# Sheet2.net
KiCad netlist of a schematic drawn in Altium Designer
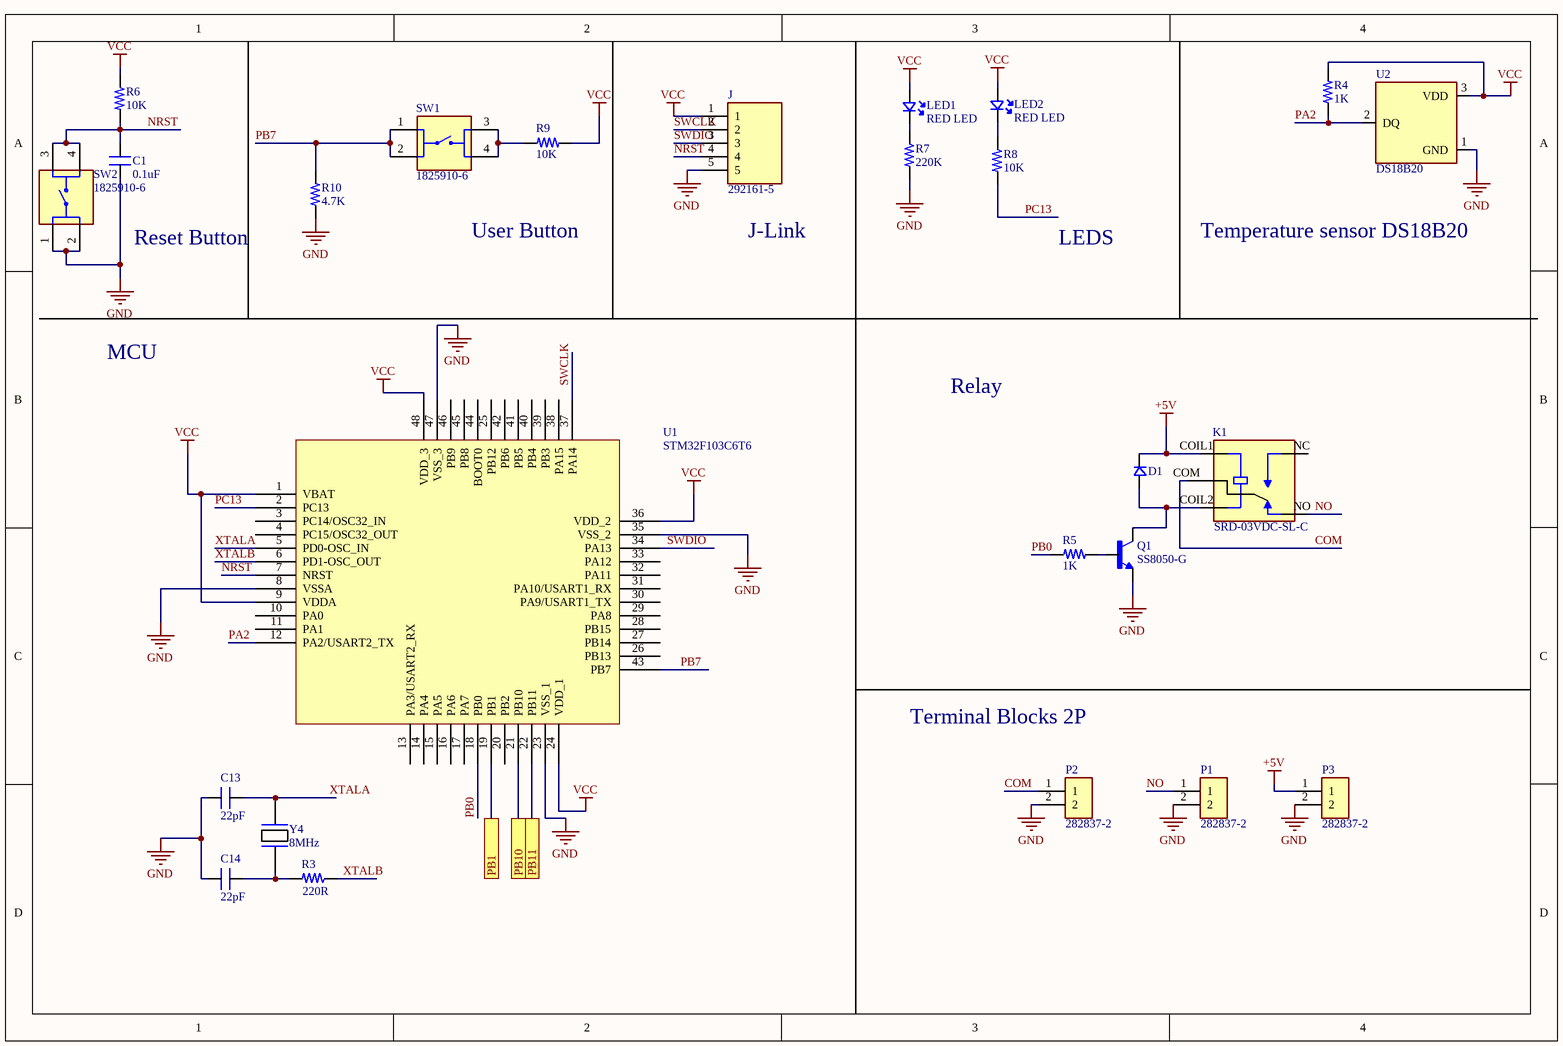
[diagram p0: Sheet2.SchDoc]

(export (version "E")
  (design (tool "Eeschema 10.0.6"))
  (components
    (comp (ref "C1")
      (value "0.1uF")
      (footprint "CAP_0805")
      (description "0.1µF ±5% 50V Ceramic Capacitor X7R 0805 (2012 Metric)")
      (fields
        (field (name "MANUFACTURER") "KEMET")
        (field (name "MANUFACTURING PART NUMBER") "C0805C104J5RACTU")
      )
      (libsource (lib "STM_SCH_LIB") (part "CAP_0.1uF-50V-5%-0805"))
    )
    (comp (ref "C13")
      (value "22pF")
      (footprint "CAP_0805")
      (description "22pF ±5% 50V Ceramic Capacitor C0G, NP0 0805 (2012 Metric)")
      (fields
        (field (name "MANUFACTURER") "KEMET")
        (field (name "MANUFACTURER PART NUMBER") "C0805C220J5GACTU")
      )
      (libsource (lib "STM_SCH_LIB") (part "CAP_22pF-50V-5%-0805"))
    )
    (comp (ref "C14")
      (value "22pF")
      (footprint "CAP_0805")
      (description "22pF ±5% 50V Ceramic Capacitor C0G, NP0 0805 (2012 Metric)")
      (fields
        (field (name "MANUFACTURER") "KEMET")
        (field (name "MANUFACTURER PART NUMBER") "C0805C220J5GACTU")
      )
      (libsource (lib "STM_SCH_LIB") (part "CAP_22pF-50V-5%-0805"))
    )
    (comp (ref "D1")
      (value "~")
      (footprint "DIOAD829W49L456D191")
      (description "Diode Standard 75V 200mA Surface Mount SOD-523F")
      (libsource (lib "Power_Plug") (part "1N4148"))
    )
    (comp (ref "J")
      (value "292161-5")
      (footprint "TE_292161-5")
      (description "Wire-To-Board Connector, Vertical, AMP CT Series, Through Hole, Header, 5, 2 mm")
      (fields (field (name "MF") "TE Connectivity"))
      (libsource (lib "Power_Plug") (part "292161-5"))
    )
    (comp (ref "K1")
      (value "SRD-03VDC-SL-C")
      (footprint "RELAY_SRD-03VDC-SL-C")
      (description "Relays General Purpose Non Latching 3VDC SPDT 10A (250VAC) Max 5PIN")
      (fields (field (name "MF") "Songle Relay"))
      (libsource (lib "Power_Plug") (part "SRD-03VDC-SL-C"))
    )
    (comp (ref "LED1")
      (value "RED LED")
      (footprint "LED_0805")
      (description "Red 621nm LED Indication - Discrete 2V 0805 (2012 Metric)")
      (fields
        (field (name "MANUFACTURER") "Lite-On Inc.")
        (field (name "MANUFACTURER PART NUMBER") "LTST-C170EKT")
      )
      (libsource (lib "STM_SCH_LIB") (part "LED-RED_10mA-0805"))
    )
    (comp (ref "LED2")
      (value "RED LED")
      (footprint "LED_0805")
      (description "Red 621nm LED Indication - Discrete 2V 0805 (2012 Metric)")
      (fields
        (field (name "MANUFACTURER") "Lite-On Inc.")
        (field (name "MANUFACTURER PART NUMBER") "LTST-C170EKT")
      )
      (libsource (lib "STM_SCH_LIB") (part "LED-RED_10mA-0805"))
    )
    (comp (ref "P1")
      (value "282837-2")
      (footprint "TE_282837-2")
      (description "Connector Terminal Blocks Receptacle 2 Position 5.08mm Solder Straight Thru-Hole 13.5A/Contact")
      (fields (field (name "MF") "TE Connectivity"))
      (libsource (lib "Power_Plug") (part "282837-2"))
    )
    (comp (ref "P2")
      (value "282837-2")
      (footprint "TE_282837-2")
      (description "Connector Terminal Blocks Receptacle 2 Position 5.08mm Solder Straight Thru-Hole 13.5A/Contact")
      (fields (field (name "MF") "TE Connectivity"))
      (libsource (lib "Power_Plug") (part "282837-2"))
    )
    (comp (ref "P3")
      (value "282837-2")
      (footprint "TE_282837-2")
      (description "Connector Terminal Blocks Receptacle 2 Position 5.08mm Solder Straight Thru-Hole 13.5A/Contact")
      (fields (field (name "MF") "TE Connectivity"))
      (libsource (lib "Power_Plug") (part "282837-2"))
    )
    (comp (ref "Q1")
      (value "SS8050-G")
      (footprint "TRANS_SS8050-G")
      (description "Bipolar (BJT) Transistor NPN 25 V 1.5 A 100MHz 300 mW Surface Mount SOT-23-3")
      (fields (field (name "DIGI-KEY_PART_NUMBER") "641-1790-2-ND") (field (name "MP") "SS8050G"))
      (libsource (lib "Power_Plug") (part "SS8050-G"))
    )
    (comp (ref "R3")
      (value "220R")
      (footprint "RES_0805")
      (description "220 Ohms ±1% 0.125W, 1/8W Chip Resistor 0805 (2012 Metric) Thick Film")
      (fields
        (field (name "MANUFACTURER") "TE Connectivity Passive Product")
        (field (name "MANUFACTURING PART NUMBER") "CRG0805F1K5")
      )
      (libsource (lib "Power_Plug") (part "RES_220R-0.125W-1%-0805_1_1_1"))
    )
    (comp (ref "R4")
      (value "1K")
      (footprint "RES_0805")
      (description "4.7 kOhms ±1% 0.125W, 1/8W Chip Resistor 0805 (2012 Metric) Thick Film")
      (fields
        (field (name "MANUFACTURER") "TE Connectivity Passive Product")
        (field (name "MANUFACTURING PART NUMBER") "CRG0805F1K5")
      )
      (libsource (lib "Power_Plug") (part "RES_4.7K-0.125W-1%-0805"))
    )
    (comp (ref "R5")
      (value "1K")
      (footprint "RES_0805")
      (description "10 kOhms ±1% 0.125W, 1/8W Chip Resistor 0805 (2012 Metric) Moisture Resistant Thick Film")
      (fields
        (field (name "MANUFACTURER") "Yageo")
        (field (name "MANUFACTURING PART NUMBER") "RC0805FR-0710KL")
      )
      (libsource (lib "Power_Plug") (part "RES_10K-0.125W-1%-0805"))
    )
    (comp (ref "R6")
      (value "10K")
      (footprint "RES_0805")
      (description "10 kOhms ±1% 0.125W, 1/8W Chip Resistor 0805 (2012 Metric) Moisture Resistant Thick Film")
      (fields
        (field (name "MANUFACTURER") "Yageo")
        (field (name "MANUFACTURING PART NUMBER") "RC0805FR-0710KL")
      )
      (libsource (lib "STM_SCH_LIB") (part "RES_10K-0.125W-1%-0805"))
    )
    (comp (ref "R7")
      (value "220K")
      (footprint "RES_0805")
      (description "1 kOhms ±1% 0.125W, 1/8W Chip Resistor 0805 (2012 Metric) Moisture Resistant Thick Film")
      (fields (field (name "MANUFACTURER") "垈㎵á") (field (name "MANUFACTURER PART NUMBER") "RC0805FR-071KL"))
      (libsource (lib "STM_SCH_LIB") (part "RES_1K-0.125W-1%-0805"))
    )
    (comp (ref "R8")
      (value "10K")
      (footprint "RES_0805")
      (description "10 kOhms ±1% 0.125W, 1/8W Chip Resistor 0805 (2012 Metric) Moisture Resistant Thick Film")
      (fields
        (field (name "MANUFACTURER") "Yageo")
        (field (name "MANUFACTURING PART NUMBER") "RC0805FR-0710KL")
      )
      (libsource (lib "Power_Plug") (part "RES_10K-0.125W-1%-0805"))
    )
    (comp (ref "R9")
      (value "10K")
      (footprint "RES_0805")
      (description "220 Ohms ±1% 0.125W, 1/8W Chip Resistor 0805 (2012 Metric) Thick Film")
      (fields
        (field (name "MANUFACTURER") "TE Connectivity Passive Product")
        (field (name "MANUFACTURING PART NUMBER") "CRG0805F1K5")
      )
      (libsource (lib "Power_Plug") (part "RES_220R-0.125W-1%-0805_1_1_1"))
    )
    (comp (ref "R10")
      (value "4.7K")
      (footprint "RES_0805")
      (description "4.7 kOhms ±1% 0.125W, 1/8W Chip Resistor 0805 (2012 Metric) Thick Film")
      (fields
        (field (name "MANUFACTURER") "TE Connectivity Passive Product")
        (field (name "MANUFACTURING PART NUMBER") "CRG0805F1K5")
      )
      (libsource (lib "Power_Plug") (part "RES_4.7K-0.125W-1%-0805"))
    )
    (comp (ref "SW1")
      (value "1825910-6")
      (footprint "SW_1825910-6-4")
      (description "Switch Tactile OFF (ON) SPST Round Button PC Pins 0.05A 24VDC 100000Cycles 1.57N Thru-Hole Loose")
      (libsource (lib "Power_Plug") (part "1825910-6"))
    )
    (comp (ref "SW2")
      (value "1825910-6")
      (footprint "SW_1825910-6-4")
      (description "Switch Tactile OFF (ON) SPST Round Button PC Pins 0.05A 24VDC 100000Cycles 1.57N Thru-Hole Loose")
      (libsource (lib "") (part "1825910-6_1"))
    )
    (comp (ref "U1")
      (value "STM32F103C6T6")
      (footprint "LQFP-48_19.6_393_58X11_SMD")
      (description "ARM® Cortex®-M3 STM32F1 Microcontroller IC 32-Bit 72MHz 64KB (64K x 8) FLASH")
      (fields
        (field (name "MANUFACTURER") "STMicroelectronics")
        (field (name "MANUFACTURER PART NUMBER") "STM32F103C8T6")
      )
      (libsource (lib "Power_Plug") (part "IC-STM32F103C6T6 _1"))
    )
    (comp (ref "U2")
      (value "DS18B20")
      (footprint "TO-92-TO92127P495H2044-3")
      (description "Temperature Sensor Digital, Local -55Â°C ~ 125Â°C 12 b 8-uMAX-EP¦8-uSOP-EP")
      (fields (field (name "MF") "Maxim"))
      (libsource (lib "Power_Plug") (part "DS18B20"))
    )
    (comp (ref "Y4")
      (value "8MHz")
      (footprint "XTAL_314_240X47_SMD")
      (description "Crystals 8MHz 22pF -20C 70C")
      (fields
        (field (name "MANUFACTURER") "IQD Frequency Products")
        (field (name "MANUFACTURING PART NUMBER") "LFXTAL030234Reel")
      )
      (libsource (lib "STM_SCH_LIB") (part "XTAL_8MHZ-LFXTAL030234"))
    )
  )
  (nets
    (net (code "1") (name "+5V") (class "Default")
      (node (ref "D1") (pin "C") (pinfunction "C_C") (pintype "passive"))
      (node (ref "K1") (pin "COIL1") (pinfunction "COIL1_COIL1") (pintype "passive"))
      (node (ref "P3") (pin "1") (pinfunction "1_1") (pintype "passive"))
    )
    (net (code "2") (name "/COM") (class "Default")
      (node (ref "K1") (pin "COM") (pinfunction "COM_COM") (pintype "passive"))
      (node (ref "P2") (pin "1") (pinfunction "1_1") (pintype "passive"))
    )
    (net (code "3") (name "/NO") (class "Default")
      (node (ref "K1") (pin "NO") (pinfunction "NO_NO") (pintype "passive"))
      (node (ref "P1") (pin "1") (pinfunction "1_1") (pintype "passive"))
    )
    (net (code "4") (name "/NRST") (class "Default")
      (node (ref "C1") (pin "2") (pinfunction "2_2") (pintype "passive"))
      (node (ref "J") (pin "4") (pinfunction "4_4") (pintype "passive"))
      (node (ref "R6") (pin "1") (pinfunction "1_1") (pintype "passive"))
      (node (ref "SW2") (pin "3") (pinfunction "3_3") (pintype "passive"))
      (node (ref "SW2") (pin "4") (pinfunction "4_4") (pintype "passive"))
      (node (ref "U1") (pin "7") (pinfunction "NRST_7") (pintype "passive"))
    )
    (net (code "5") (name "/PA2") (class "Default")
      (node (ref "R4") (pin "1") (pinfunction "1_1") (pintype "passive"))
      (node (ref "U1") (pin "12") (pinfunction "PA2/USART2_TX_12") (pintype "passive"))
      (node (ref "U2") (pin "2") (pinfunction "DQ_2") (pintype "passive"))
    )
    (net (code "6") (name "/PB0") (class "Default")
      (node (ref "R5") (pin "1") (pinfunction "1_1") (pintype "passive"))
      (node (ref "U1") (pin "18") (pinfunction "PB0_18") (pintype "passive"))
    )
    (net (code "7") (name "/PB1") (class "Default")
      (node (ref "U1") (pin "19") (pinfunction "PB1_19") (pintype "passive"))
    )
    (net (code "8") (name "/PB7") (class "Default")
      (node (ref "R10") (pin "2") (pinfunction "2_2") (pintype "passive"))
      (node (ref "SW1") (pin "1") (pinfunction "1_1") (pintype "passive"))
      (node (ref "SW1") (pin "2") (pinfunction "2_2") (pintype "passive"))
      (node (ref "U1") (pin "43") (pinfunction "PB7_43") (pintype "passive"))
    )
    (net (code "9") (name "/PB10") (class "Default")
      (node (ref "U1") (pin "21") (pinfunction "PB10_21") (pintype "passive"))
    )
    (net (code "10") (name "/PB11") (class "Default")
      (node (ref "U1") (pin "22") (pinfunction "PB11_22") (pintype "passive"))
    )
    (net (code "11") (name "/PC13") (class "Default")
      (node (ref "R8") (pin "1") (pinfunction "1_1") (pintype "passive"))
      (node (ref "U1") (pin "2") (pinfunction "PC13_2") (pintype "passive"))
    )
    (net (code "12") (name "/SWCLK") (class "Default")
      (node (ref "J") (pin "2") (pinfunction "2_2") (pintype "passive"))
      (node (ref "U1") (pin "37") (pinfunction "PA14_37") (pintype "passive"))
    )
    (net (code "13") (name "/SWDIO") (class "Default")
      (node (ref "J") (pin "3") (pinfunction "3_3") (pintype "passive"))
      (node (ref "U1") (pin "34") (pinfunction "PA13_34") (pintype "passive"))
    )
    (net (code "14") (name "/XTALA") (class "Default")
      (node (ref "C13") (pin "2") (pinfunction "2_2") (pintype "passive"))
      (node (ref "U1") (pin "5") (pinfunction "PD0-OSC_IN_5") (pintype "passive"))
      (node (ref "Y4") (pin "1") (pinfunction "1_1") (pintype "passive"))
    )
    (net (code "15") (name "/XTALB") (class "Default")
      (node (ref "R3") (pin "2") (pinfunction "2_2") (pintype "passive"))
      (node (ref "U1") (pin "6") (pinfunction "PD1-OSC_OUT_6") (pintype "passive"))
    )
    (net (code "16") (name "GND") (class "Default")
      (node (ref "C1") (pin "1") (pinfunction "1_1") (pintype "passive"))
      (node (ref "C13") (pin "1") (pinfunction "1_1") (pintype "passive"))
      (node (ref "C14") (pin "1") (pinfunction "1_1") (pintype "passive"))
      (node (ref "J") (pin "5") (pinfunction "5_5") (pintype "passive"))
      (node (ref "P1") (pin "2") (pinfunction "2_2") (pintype "passive"))
      (node (ref "P2") (pin "2") (pinfunction "2_2") (pintype "passive"))
      (node (ref "P3") (pin "2") (pinfunction "2_2") (pintype "passive"))
      (node (ref "Q1") (pin "2") (pinfunction "E_2") (pintype "passive"))
      (node (ref "R10") (pin "1") (pinfunction "1_1") (pintype "passive"))
      (node (ref "R7") (pin "1") (pinfunction "1_1") (pintype "passive"))
      (node (ref "SW2") (pin "1") (pinfunction "1_1") (pintype "passive"))
      (node (ref "SW2") (pin "2") (pinfunction "2_2") (pintype "passive"))
      (node (ref "U1") (pin "23") (pinfunction "VSS_1_23") (pintype "passive"))
      (node (ref "U1") (pin "35") (pinfunction "VSS_2_35") (pintype "passive"))
      (node (ref "U1") (pin "47") (pinfunction "VSS_3_47") (pintype "passive"))
      (node (ref "U1") (pin "8") (pinfunction "VSSA_8") (pintype "passive"))
      (node (ref "U2") (pin "1") (pinfunction "GND_1") (pintype "power_in"))
    )
    (net (code "17") (name "Net-(C14-Pad2)") (class "Default")
      (node (ref "C14") (pin "2") (pinfunction "2_2") (pintype "passive"))
      (node (ref "R3") (pin "1") (pinfunction "1_1") (pintype "passive"))
      (node (ref "Y4") (pin "2") (pinfunction "2_2") (pintype "passive"))
    )
    (net (code "18") (name "Net-(LED1-PadK)") (class "Default")
      (node (ref "LED1") (pin "K") (pinfunction "K_K") (pintype "passive"))
      (node (ref "R7") (pin "2") (pinfunction "2_2") (pintype "passive"))
    )
    (net (code "19") (name "Net-(LED2-PadK)") (class "Default")
      (node (ref "LED2") (pin "K") (pinfunction "K_K") (pintype "passive"))
      (node (ref "R8") (pin "2") (pinfunction "2_2") (pintype "passive"))
    )
    (net (code "20") (name "Net-(Q1-B)") (class "Default")
      (node (ref "Q1") (pin "1") (pinfunction "B_1") (pintype "passive"))
      (node (ref "R5") (pin "2") (pinfunction "2_2") (pintype "passive"))
    )
    (net (code "21") (name "Net-(Q1-C)") (class "Default")
      (node (ref "D1") (pin "A") (pinfunction "A_A") (pintype "passive"))
      (node (ref "K1") (pin "COIL2") (pinfunction "COIL2_COIL2") (pintype "passive"))
      (node (ref "Q1") (pin "3") (pinfunction "C_3") (pintype "passive"))
    )
    (net (code "22") (name "Net-(R9-Pad1)") (class "Default")
      (node (ref "R9") (pin "1") (pinfunction "1_1") (pintype "passive"))
      (node (ref "SW1") (pin "3") (pinfunction "3_3") (pintype "passive"))
      (node (ref "SW1") (pin "4") (pinfunction "4_4") (pintype "passive"))
    )
    (net (code "23") (name "VCC") (class "Default")
      (node (ref "J") (pin "1") (pinfunction "1_1") (pintype "passive"))
      (node (ref "LED1") (pin "A") (pinfunction "A_A") (pintype "passive"))
      (node (ref "LED2") (pin "A") (pinfunction "A_A") (pintype "passive"))
      (node (ref "R4") (pin "2") (pinfunction "2_2") (pintype "passive"))
      (node (ref "R6") (pin "2") (pinfunction "2_2") (pintype "passive"))
      (node (ref "R9") (pin "2") (pinfunction "2_2") (pintype "passive"))
      (node (ref "U1") (pin "1") (pinfunction "VBAT_1") (pintype "passive"))
      (node (ref "U1") (pin "24") (pinfunction "VDD_1_24") (pintype "passive"))
      (node (ref "U1") (pin "36") (pinfunction "VDD_2_36") (pintype "passive"))
      (node (ref "U1") (pin "48") (pinfunction "VDD_3_48") (pintype "passive"))
      (node (ref "U1") (pin "9") (pinfunction "VDDA_9") (pintype "passive"))
      (node (ref "U2") (pin "3") (pinfunction "VDD_3") (pintype "power_in"))
    )
    (net (code "24") (name "unconnected-(K1-PadNC)") (class "Default")
      (node (ref "K1") (pin "NC") (pinfunction "NC_NC") (pintype "passive"))
    )
    (net (code "25") (name "unconnected-(U1-BOOT0-Pad44)") (class "Default")
      (node (ref "U1") (pin "44") (pinfunction "BOOT0_44") (pintype "passive"))
    )
    (net (code "26") (name "unconnected-(U1-PA0-Pad10)") (class "Default")
      (node (ref "U1") (pin "10") (pinfunction "PA0_10") (pintype "passive"))
    )
    (net (code "27") (name "unconnected-(U1-PA1-Pad11)") (class "Default")
      (node (ref "U1") (pin "11") (pinfunction "PA1_11") (pintype "passive"))
    )
    (net (code "28") (name "unconnected-(U1-PA3{slash}USART2_RX-Pad13)") (class "Default")
      (node (ref "U1") (pin "13") (pinfunction "PA3/USART2_RX_13") (pintype "passive"))
    )
    (net (code "29") (name "unconnected-(U1-PA4-Pad14)") (class "Default")
      (node (ref "U1") (pin "14") (pinfunction "PA4_14") (pintype "passive"))
    )
    (net (code "30") (name "unconnected-(U1-PA5-Pad15)") (class "Default")
      (node (ref "U1") (pin "15") (pinfunction "PA5_15") (pintype "passive"))
    )
    (net (code "31") (name "unconnected-(U1-PA6-Pad16)") (class "Default")
      (node (ref "U1") (pin "16") (pinfunction "PA6_16") (pintype "passive"))
    )
    (net (code "32") (name "unconnected-(U1-PA7-Pad17)") (class "Default")
      (node (ref "U1") (pin "17") (pinfunction "PA7_17") (pintype "passive"))
    )
    (net (code "33") (name "unconnected-(U1-PA8-Pad29)") (class "Default")
      (node (ref "U1") (pin "29") (pinfunction "PA8_29") (pintype "passive"))
    )
    (net (code "34") (name "unconnected-(U1-PA9{slash}USART1_TX-Pad30)") (class "Default")
      (node (ref "U1") (pin "30") (pinfunction "PA9/USART1_TX_30") (pintype "passive"))
    )
    (net (code "35") (name "unconnected-(U1-PA10{slash}USART1_RX-Pad31)") (class "Default")
      (node (ref "U1") (pin "31") (pinfunction "PA10/USART1_RX_31") (pintype "passive"))
    )
    (net (code "36") (name "unconnected-(U1-PA11-Pad32)") (class "Default")
      (node (ref "U1") (pin "32") (pinfunction "PA11_32") (pintype "passive"))
    )
    (net (code "37") (name "unconnected-(U1-PA12-Pad33)") (class "Default")
      (node (ref "U1") (pin "33") (pinfunction "PA12_33") (pintype "passive"))
    )
    (net (code "38") (name "unconnected-(U1-PA15-Pad38)") (class "Default")
      (node (ref "U1") (pin "38") (pinfunction "PA15_38") (pintype "passive"))
    )
    (net (code "39") (name "unconnected-(U1-PB2-Pad20)") (class "Default")
      (node (ref "U1") (pin "20") (pinfunction "PB2_20") (pintype "passive"))
    )
    (net (code "40") (name "unconnected-(U1-PB3-Pad39)") (class "Default")
      (node (ref "U1") (pin "39") (pinfunction "PB3_39") (pintype "passive"))
    )
    (net (code "41") (name "unconnected-(U1-PB4-Pad40)") (class "Default")
      (node (ref "U1") (pin "40") (pinfunction "PB4_40") (pintype "passive"))
    )
    (net (code "42") (name "unconnected-(U1-PB5-Pad41)") (class "Default")
      (node (ref "U1") (pin "41") (pinfunction "PB5_41") (pintype "passive"))
    )
    (net (code "43") (name "unconnected-(U1-PB6-Pad42)") (class "Default")
      (node (ref "U1") (pin "42") (pinfunction "PB6_42") (pintype "passive"))
    )
    (net (code "44") (name "unconnected-(U1-PB8-Pad45)") (class "Default")
      (node (ref "U1") (pin "45") (pinfunction "PB8_45") (pintype "passive"))
    )
    (net (code "45") (name "unconnected-(U1-PB9-Pad46)") (class "Default")
      (node (ref "U1") (pin "46") (pinfunction "PB9_46") (pintype "passive"))
    )
    (net (code "46") (name "unconnected-(U1-PB12-Pad25)") (class "Default")
      (node (ref "U1") (pin "25") (pinfunction "PB12_25") (pintype "passive"))
    )
    (net (code "47") (name "unconnected-(U1-PB13-Pad26)") (class "Default")
      (node (ref "U1") (pin "26") (pinfunction "PB13_26") (pintype "passive"))
    )
    (net (code "48") (name "unconnected-(U1-PB14-Pad27)") (class "Default")
      (node (ref "U1") (pin "27") (pinfunction "PB14_27") (pintype "passive"))
    )
    (net (code "49") (name "unconnected-(U1-PB15-Pad28)") (class "Default")
      (node (ref "U1") (pin "28") (pinfunction "PB15_28") (pintype "passive"))
    )
    (net (code "50") (name "unconnected-(U1-PC14{slash}OSC32_IN-Pad3)") (class "Default")
      (node (ref "U1") (pin "3") (pinfunction "PC14/OSC32_IN_3") (pintype "passive"))
    )
    (net (code "51") (name "unconnected-(U1-PC15{slash}OSC32_OUT-Pad4)") (class "Default")
      (node (ref "U1") (pin "4") (pinfunction "PC15/OSC32_OUT_4") (pintype "passive"))
    )
  )
)
